# MicroMultimeter_PHONECNT_Sch.net
KiCad netlist of a schematic drawn in Altium Designer
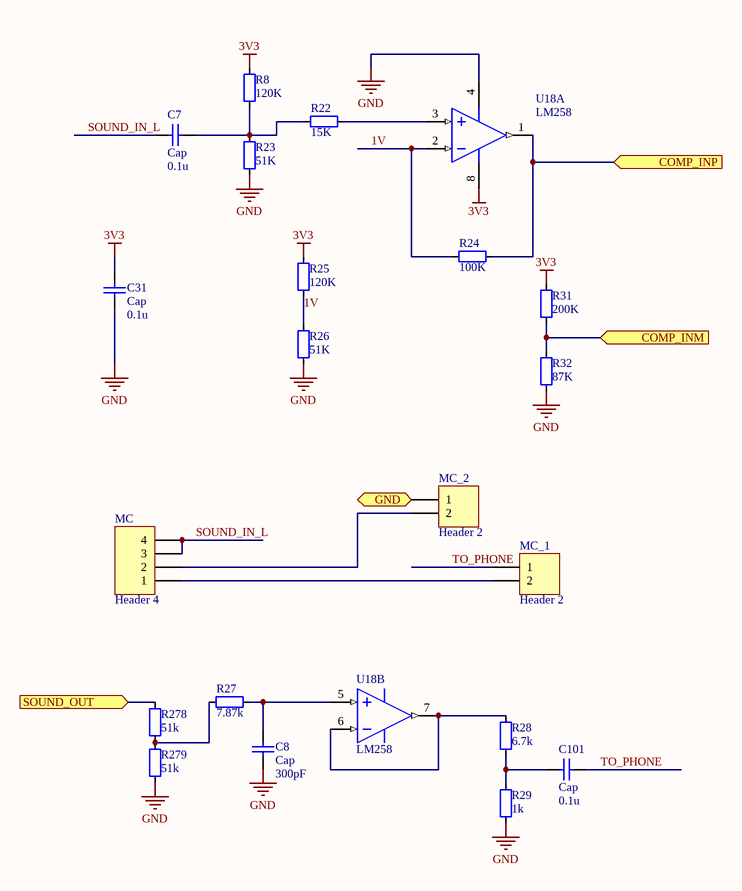
[diagram p0: MicroMultimeter_PHONECNT_Sch.SchDoc]

(export (version "E")
  (design (tool "Eeschema 10.0.6"))
  (components
    (comp (ref "C7")
      (value "Cap")
      (footprint "CAP_0603")
      (description "Capacitor")
      (fields (field (name "ALTIUM_VALUE") "0.1u") (field (name "PUBLISHER") "Altium Limited"))
      (libsource (lib "Miscellaneous Devices") (part "Cap"))
    )
    (comp (ref "C8")
      (value "Cap")
      (footprint "CAP_0603")
      (description "Capacitor")
      (fields (field (name "ALTIUM_VALUE") "300pF") (field (name "PUBLISHER") "Altium Limited"))
      (libsource (lib "Miscellaneous Devices") (part "Cap"))
    )
    (comp (ref "C31")
      (value "Cap")
      (footprint "CAP_0603")
      (description "Capacitor")
      (fields (field (name "ALTIUM_VALUE") "0.1u") (field (name "PUBLISHER") "Altium Limited"))
      (libsource (lib "Miscellaneous Devices") (part "Cap"))
    )
    (comp (ref "C101")
      (value "Cap")
      (footprint "CAP_0603")
      (description "Capacitor")
      (fields (field (name "ALTIUM_VALUE") "0.1u") (field (name "PUBLISHER") "Altium Limited"))
      (libsource (lib "Miscellaneous Devices") (part "Cap"))
    )
    (comp (ref "MC")
      (value "Header 4")
      (footprint "MIRCOPHONE_2")
      (description "Header, 4-Pin")
      (fields (field (name "PUBLISHER") "Altium Limited"))
      (libsource (lib "Miscellaneous Connectors") (part "Header 4"))
    )
    (comp (ref "MC_1")
      (value "Header 2")
      (footprint "HDR1X2")
      (description "Header, 2-Pin")
      (fields (field (name "PUBLISHER") "Altium Limited"))
      (libsource (lib "Miscellaneous Connectors") (part "Header 2"))
    )
    (comp (ref "MC_2")
      (value "Header 2")
      (footprint "HDR1X2")
      (description "Header, 2-Pin")
      (fields (field (name "PUBLISHER") "Altium Limited"))
      (libsource (lib "Miscellaneous Connectors") (part "Header 2"))
    )
    (comp (ref "R8")
      (value "120K")
      (footprint "RES_0603")
      (description "Resistor")
      (fields (field (name "Comment") "Res_0603"))
      (libsource (lib "") (part "Res_0603_2"))
    )
    (comp (ref "R22")
      (value "15K")
      (footprint "RES_0603")
      (description "Resistor")
      (fields (field (name "Comment") "Res_0603"))
      (libsource (lib "") (part "Res_0603_1"))
    )
    (comp (ref "R23")
      (value "51K")
      (footprint "RES_0603")
      (description "Resistor")
      (fields (field (name "Comment") "Res_0603"))
      (libsource (lib "") (part "Res_0603_2"))
    )
    (comp (ref "R24")
      (value "100K")
      (footprint "RES_0603")
      (description "Resistor")
      (fields (field (name "Comment") "Res_0603"))
      (libsource (lib "") (part "Res_0603_1"))
    )
    (comp (ref "R25")
      (value "120K")
      (footprint "RES_0603")
      (description "Resistor")
      (fields (field (name "Comment") "Res_0603"))
      (libsource (lib "") (part "Res_0603_2"))
    )
    (comp (ref "R26")
      (value "51K")
      (footprint "RES_0603")
      (description "Resistor")
      (fields (field (name "Comment") "Res_0603"))
      (libsource (lib "") (part "Res_0603_2"))
    )
    (comp (ref "R27")
      (value "7.87k")
      (footprint "RES_0603")
      (description "Resistor")
      (fields (field (name "Comment") "Res_0603"))
      (libsource (lib "") (part "Res_0603_1"))
    )
    (comp (ref "R28")
      (value "6.7k")
      (footprint "RES_0603")
      (description "Resistor")
      (fields (field (name "Comment") "Res_0603"))
      (libsource (lib "SCH_Passive") (part "Res_0603"))
    )
    (comp (ref "R29")
      (value "1k")
      (footprint "RES_0603")
      (description "Resistor")
      (fields (field (name "Comment") "Res_0603"))
      (libsource (lib "SCH_Passive") (part "Res_0603"))
    )
    (comp (ref "R31")
      (value "200K")
      (footprint "RES_0603")
      (description "Resistor")
      (fields (field (name "Comment") "Res_0603"))
      (libsource (lib "") (part "Res_0603_2"))
    )
    (comp (ref "R32")
      (value "87K")
      (footprint "RES_0603")
      (description "Resistor")
      (fields (field (name "Comment") "Res_0603"))
      (libsource (lib "") (part "Res_0603_2"))
    )
    (comp (ref "R278")
      (value "51k")
      (footprint "RES_0603")
      (description "Resistor")
      (fields (field (name "Comment") "Res_0603"))
      (libsource (lib "SCH_Passive") (part "Res_0603"))
    )
    (comp (ref "R279")
      (value "51k")
      (footprint "RES_0603")
      (description "Resistor")
      (fields (field (name "Comment") "Res_0603"))
      (libsource (lib "SCH_Passive") (part "Res_0603"))
    )
    (comp (ref "U18")
      (value "LM258")
      (footprint "SOP-8")
      (description "Amplifier")
      (libsource (lib "MicroMultimeter_SIGNAL_Sch_Lib") (part "LM258"))
    )
  )
  (nets
    (net (code "1") (name "/1V") (class "Default")
      (node (ref "R24") (pin "2") (pinfunction "2_2") (pintype "passive"))
      (node (ref "R25") (pin "1") (pinfunction "1_1") (pintype "passive"))
      (node (ref "R26") (pin "2") (pinfunction "2_2") (pintype "passive"))
      (node (ref "U18") (pin "2") (pinfunction "IN-_2") (pintype "input"))
    )
    (net (code "2") (name "/COMP_INM") (class "Default")
      (node (ref "R31") (pin "1") (pinfunction "1_1") (pintype "passive"))
      (node (ref "R32") (pin "2") (pinfunction "2_2") (pintype "passive"))
    )
    (net (code "3") (name "/COMP_INP") (class "Default")
      (node (ref "R24") (pin "1") (pinfunction "1_1") (pintype "passive"))
      (node (ref "U18") (pin "1") (pinfunction "OUT_1") (pintype "output"))
    )
    (net (code "4") (name "/SOUND_IN_L") (class "Default")
      (node (ref "C7") (pin "1") (pinfunction "1_1") (pintype "passive"))
      (node (ref "MC") (pin "3") (pinfunction "3_3") (pintype "passive"))
      (node (ref "MC") (pin "4") (pinfunction "4_4") (pintype "passive"))
    )
    (net (code "5") (name "/SOUND_OUT") (class "Default")
      (node (ref "R278") (pin "1") (pinfunction "1_1") (pintype "passive"))
    )
    (net (code "6") (name "/TO_PHONE") (class "Default")
      (node (ref "C101") (pin "2") (pinfunction "2_2") (pintype "passive"))
      (node (ref "MC_1") (pin "1") (pinfunction "1_1") (pintype "passive"))
    )
    (net (code "7") (name "3V3") (class "Default")
      (node (ref "C31") (pin "2") (pinfunction "2_2") (pintype "passive"))
      (node (ref "R25") (pin "2") (pinfunction "2_2") (pintype "passive"))
      (node (ref "R31") (pin "2") (pinfunction "2_2") (pintype "passive"))
      (node (ref "R8") (pin "2") (pinfunction "2_2") (pintype "passive"))
      (node (ref "U18") (pin "8") (pinfunction "V+_8") (pintype "power_in"))
    )
    (net (code "8") (name "GND") (class "Default")
      (node (ref "C31") (pin "1") (pinfunction "1_1") (pintype "passive"))
      (node (ref "C8") (pin "1") (pinfunction "1_1") (pintype "passive"))
      (node (ref "MC_2") (pin "1") (pinfunction "1_1") (pintype "passive"))
      (node (ref "R23") (pin "1") (pinfunction "1_1") (pintype "passive"))
      (node (ref "R26") (pin "1") (pinfunction "1_1") (pintype "passive"))
      (node (ref "R279") (pin "2") (pinfunction "2_2") (pintype "passive"))
      (node (ref "R29") (pin "2") (pinfunction "2_2") (pintype "passive"))
      (node (ref "R32") (pin "1") (pinfunction "1_1") (pintype "passive"))
      (node (ref "U18") (pin "4") (pinfunction "V-_4") (pintype "power_in"))
    )
    (net (code "9") (name "Net-(C7-Pad2)") (class "Default")
      (node (ref "C7") (pin "2") (pinfunction "2_2") (pintype "passive"))
      (node (ref "R22") (pin "2") (pinfunction "2_2") (pintype "passive"))
      (node (ref "R23") (pin "2") (pinfunction "2_2") (pintype "passive"))
      (node (ref "R8") (pin "1") (pinfunction "1_1") (pintype "passive"))
    )
    (net (code "10") (name "Net-(C101-Pad1)") (class "Default")
      (node (ref "C101") (pin "1") (pinfunction "1_1") (pintype "passive"))
      (node (ref "R28") (pin "2") (pinfunction "2_2") (pintype "passive"))
      (node (ref "R29") (pin "1") (pinfunction "1_1") (pintype "passive"))
    )
    (net (code "11") (name "Net-(MC-Pad1)") (class "Default")
      (node (ref "MC") (pin "1") (pinfunction "1_1") (pintype "passive"))
      (node (ref "MC_1") (pin "2") (pinfunction "2_2") (pintype "passive"))
    )
    (net (code "12") (name "Net-(MC-Pad2)") (class "Default")
      (node (ref "MC") (pin "2") (pinfunction "2_2") (pintype "passive"))
      (node (ref "MC_2") (pin "2") (pinfunction "2_2") (pintype "passive"))
    )
    (net (code "13") (name "Net-(R27-Pad2)") (class "Default")
      (node (ref "R27") (pin "2") (pinfunction "2_2") (pintype "passive"))
      (node (ref "R278") (pin "2") (pinfunction "2_2") (pintype "passive"))
      (node (ref "R279") (pin "1") (pinfunction "1_1") (pintype "passive"))
    )
    (net (code "14") (name "Net-(U18A-IN+)") (class "Default")
      (node (ref "R22") (pin "1") (pinfunction "1_1") (pintype "passive"))
      (node (ref "U18") (pin "3") (pinfunction "IN+_3") (pintype "input"))
    )
    (net (code "15") (name "Net-(U18B-IN+)") (class "Default")
      (node (ref "C8") (pin "2") (pinfunction "2_2") (pintype "passive"))
      (node (ref "R27") (pin "1") (pinfunction "1_1") (pintype "passive"))
      (node (ref "U18") (pin "5") (pinfunction "IN+_5") (pintype "input"))
    )
    (net (code "16") (name "Net-(U18B-IN-)") (class "Default")
      (node (ref "R28") (pin "1") (pinfunction "1_1") (pintype "passive"))
      (node (ref "U18") (pin "6") (pinfunction "IN-_6") (pintype "input"))
      (node (ref "U18") (pin "7") (pinfunction "OUT_7") (pintype "output"))
    )
  )
)
